# SCH_dupe_2026-03-27.net
KiCad netlist of a schematic drawn in EasyEDA
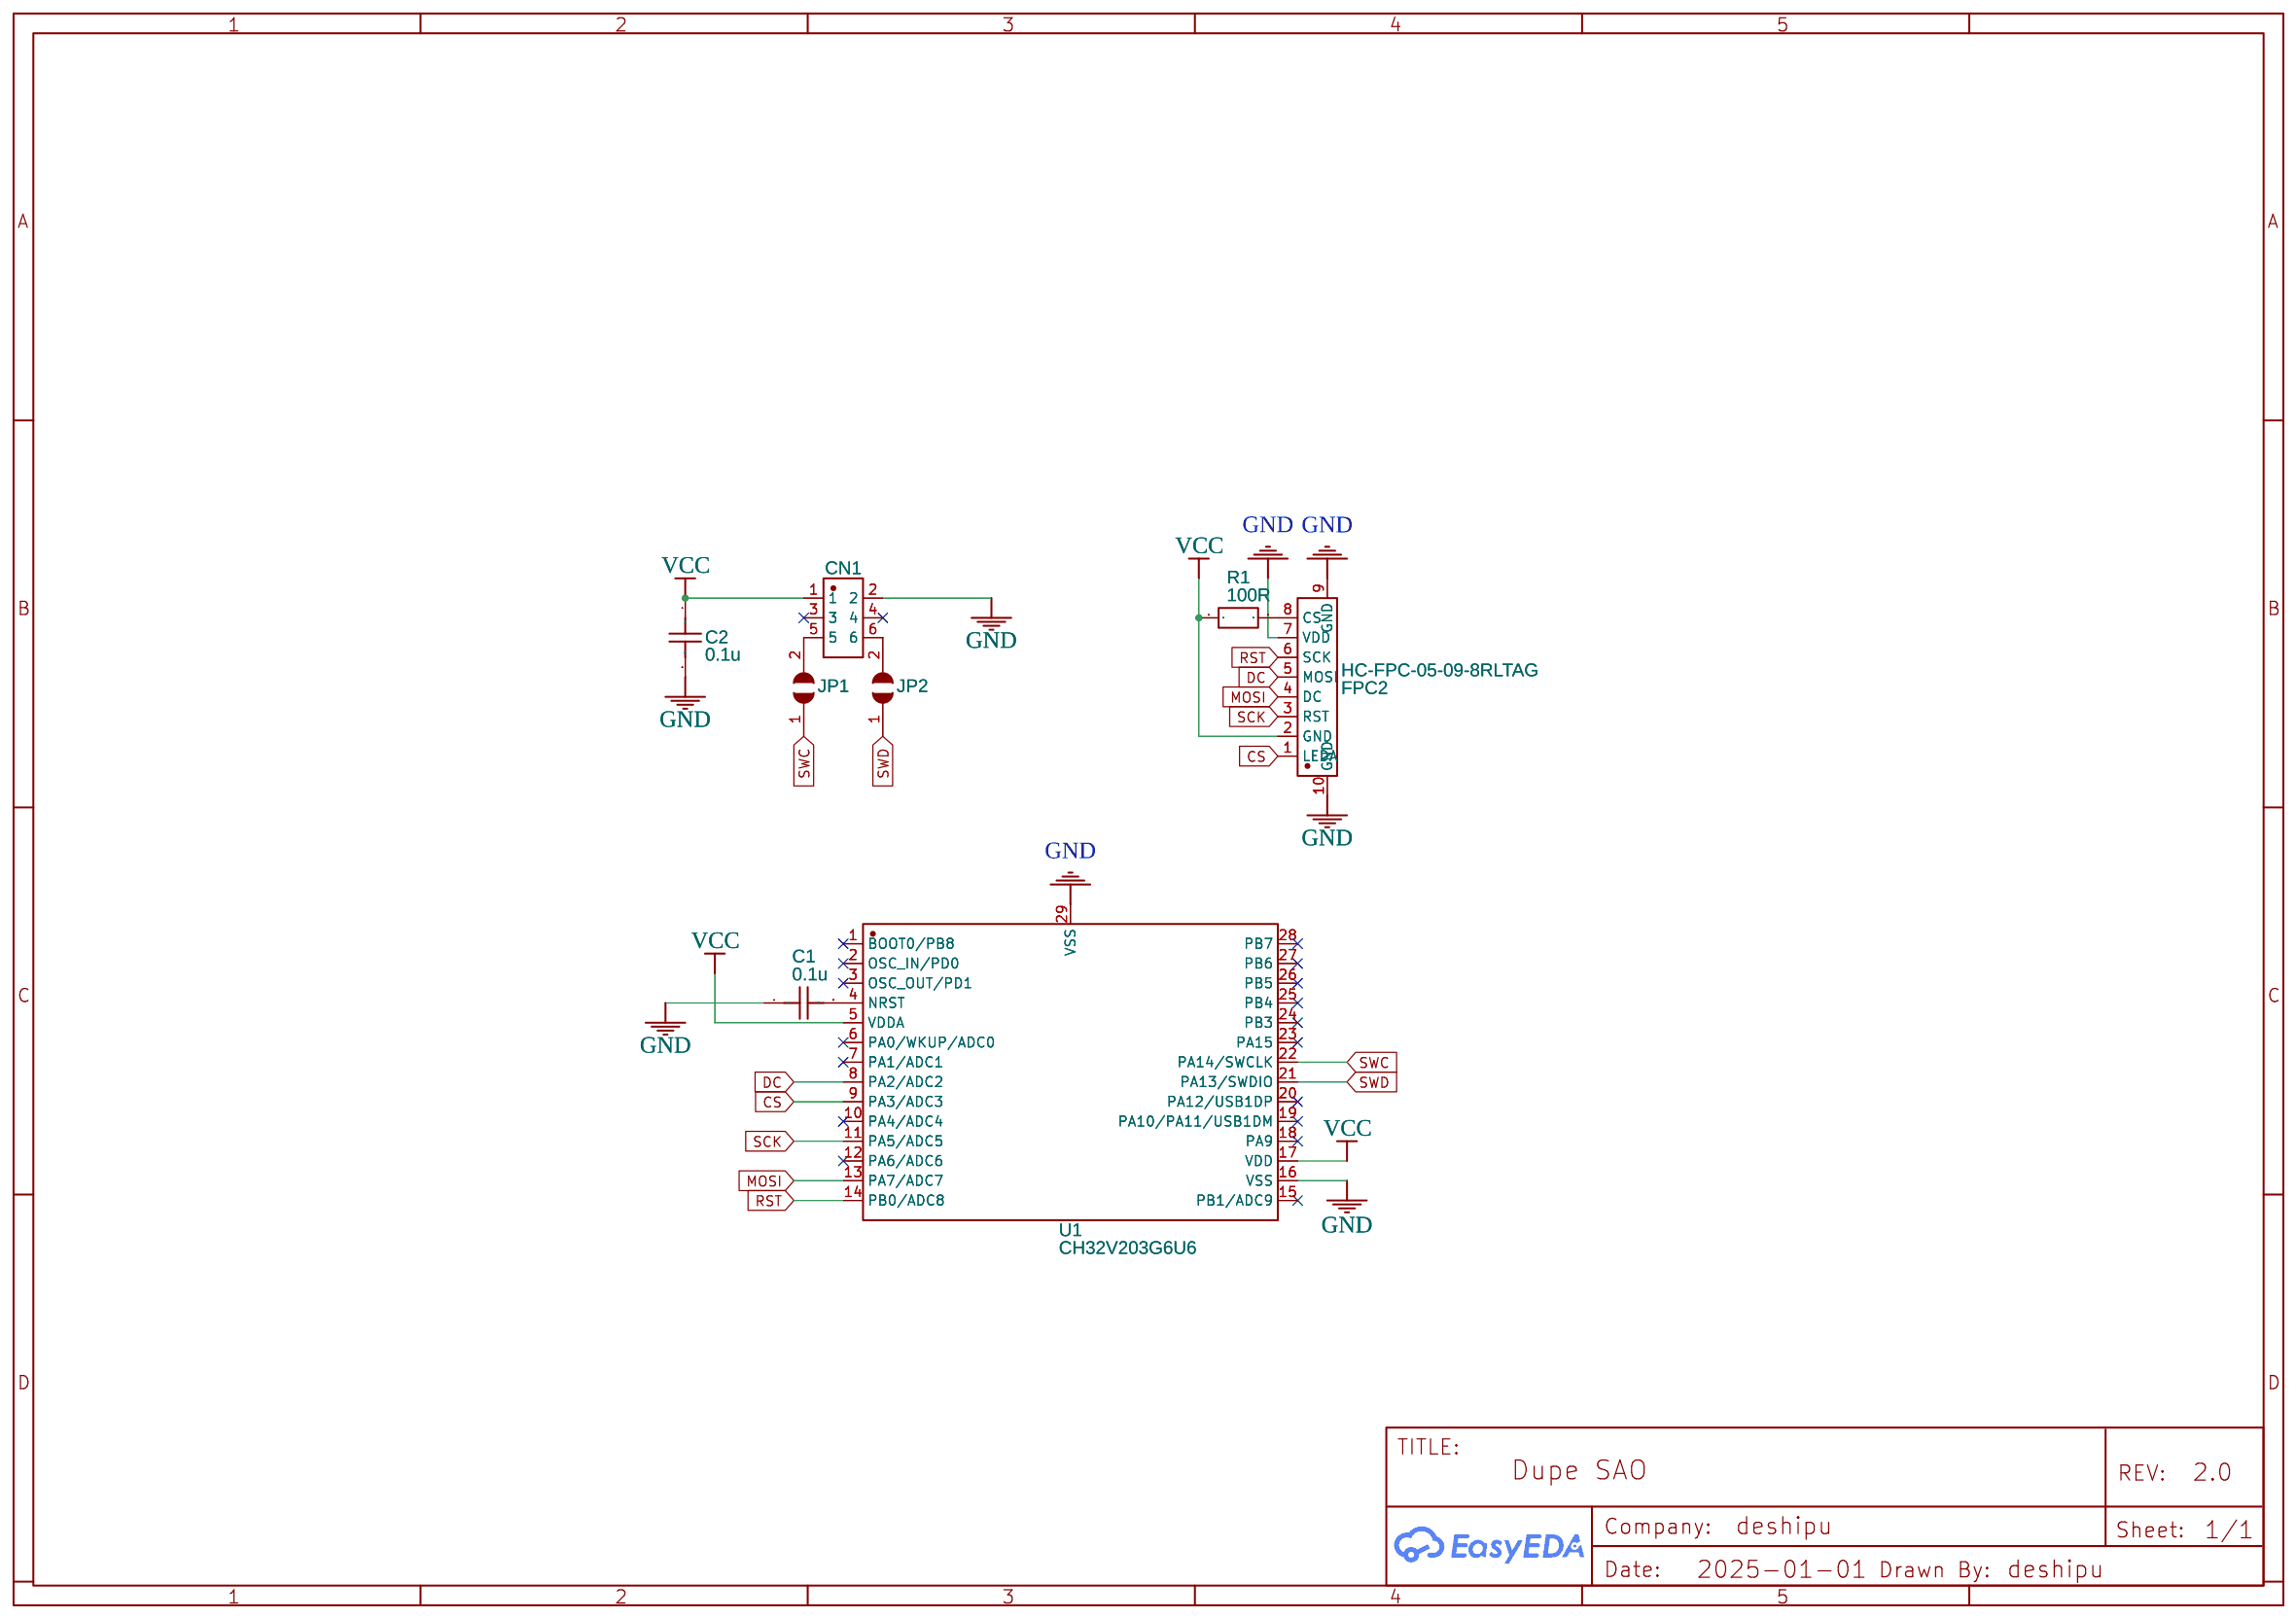
[diagram p0: schematic sheet]

(export (version "E")
  (design (tool "Eeschema 10.0.6"))
  (components
    (comp (ref "C1") (value "0.1u") (libsource (lib "") (part "C_0603_US")))
    (comp (ref "C2") (value "0.1u") (libsource (lib "") (part "C_0603_US_1")))
    (comp (ref "CN1")
      (value "BH254VS-6P")
      (fields (field (name "Manufacturer") "XFCN(兴飞)"))
      (libsource (lib "") (part "BH254VS-6P"))
    )
    (comp (ref "FPC2")
      (value "HC-FPC-05-09-8RLTAG")
      (fields (field (name "Manufacturer") "HCTL(华灿天禄)"))
      (libsource (lib "") (part "HC-FPC-05-09-8RLTAG"))
    )
    (comp (ref "JP1")
      (value "JUMPER-1-WAY-RocketScreamKicadLibrary")
      (libsource (lib "") (part "JUMPER-1-WAY-RocketScreamKicadLibrary"))
    )
    (comp (ref "JP2")
      (value "JUMPER-1-WAY-RocketScreamKicadLibrary")
      (libsource (lib "") (part "JUMPER-1-WAY-RocketScreamKicadLibrary"))
    )
    (comp (ref "R1") (value "100R") (libsource (lib "") (part "R_0603_EU")))
    (comp (ref "U1")
      (value "CH32V203G6U6")
      (fields (field (name "Manufacturer") "WCH(南京沁恒)"))
      (libsource (lib "") (part "CH32V203G6U6"))
    )
  )
  (nets
    (net (code "1") (name "CS") (class "Default")
      (node (ref "FPC2") (pin "1") (pinfunction "LEDA_1") (pintype "unspecified"))
      (node (ref "U1") (pin "9") (pinfunction "PA3/ADC3_9") (pintype "unspecified"))
    )
    (net (code "2") (name "DC") (class "Default")
      (node (ref "FPC2") (pin "5") (pinfunction "MOSI_5") (pintype "unspecified"))
      (node (ref "U1") (pin "8") (pinfunction "PA2/ADC2_8") (pintype "unspecified"))
    )
    (net (code "3") (name "GND") (class "Default")
      (node (ref "C1") (pin "1") (pinfunction "1_1") (pintype "unspecified"))
      (node (ref "C2") (pin "2") (pinfunction "2_2") (pintype "unspecified"))
      (node (ref "CN1") (pin "2") (pinfunction "2_2") (pintype "unspecified"))
      (node (ref "FPC2") (pin "10") (pinfunction "GND_10") (pintype "unspecified"))
      (node (ref "FPC2") (pin "7") (pinfunction "VDD_7") (pintype "unspecified"))
      (node (ref "FPC2") (pin "9") (pinfunction "GND_9") (pintype "unspecified"))
      (node (ref "U1") (pin "16") (pinfunction "VSS_16") (pintype "unspecified"))
      (node (ref "U1") (pin "29") (pinfunction "VSS_29") (pintype "unspecified"))
    )
    (net (code "4") (name "MOSI") (class "Default")
      (node (ref "FPC2") (pin "4") (pinfunction "DC_4") (pintype "unspecified"))
      (node (ref "U1") (pin "13") (pinfunction "PA7/ADC7_13") (pintype "unspecified"))
    )
    (net (code "5") (name "Net-(CN1-Pad5)") (class "Default")
      (node (ref "CN1") (pin "5") (pinfunction "5_5") (pintype "unspecified"))
      (node (ref "JP1") (pin "2") (pintype "unspecified"))
    )
    (net (code "6") (name "Net-(CN1-Pad6)") (class "Default")
      (node (ref "CN1") (pin "6") (pinfunction "6_6") (pintype "unspecified"))
      (node (ref "JP2") (pin "2") (pintype "unspecified"))
    )
    (net (code "7") (name "Net-(FPC2-CS)") (class "Default")
      (node (ref "FPC2") (pin "8") (pinfunction "CS_8") (pintype "unspecified"))
      (node (ref "R1") (pin "2") (pinfunction "2_2") (pintype "unspecified"))
    )
    (net (code "8") (name "Net-(U1-NRST)") (class "Default")
      (node (ref "C1") (pin "2") (pinfunction "2_2") (pintype "unspecified"))
      (node (ref "U1") (pin "4") (pinfunction "NRST_4") (pintype "unspecified"))
    )
    (net (code "9") (name "RST") (class "Default")
      (node (ref "FPC2") (pin "6") (pinfunction "SCK_6") (pintype "unspecified"))
      (node (ref "U1") (pin "14") (pinfunction "PB0/ADC8_14") (pintype "unspecified"))
    )
    (net (code "10") (name "SCK") (class "Default")
      (node (ref "FPC2") (pin "3") (pinfunction "RST_3") (pintype "unspecified"))
      (node (ref "U1") (pin "11") (pinfunction "PA5/ADC5_11") (pintype "unspecified"))
    )
    (net (code "11") (name "SWC") (class "Default")
      (node (ref "JP1") (pin "1") (pintype "unspecified"))
      (node (ref "U1") (pin "22") (pinfunction "PA14/SWCLK_22") (pintype "unspecified"))
    )
    (net (code "12") (name "SWD") (class "Default")
      (node (ref "JP2") (pin "1") (pintype "unspecified"))
      (node (ref "U1") (pin "21") (pinfunction "PA13/SWDIO_21") (pintype "unspecified"))
    )
    (net (code "13") (name "VCC") (class "Default")
      (node (ref "C2") (pin "1") (pinfunction "1_1") (pintype "unspecified"))
      (node (ref "CN1") (pin "1") (pinfunction "1_1") (pintype "unspecified"))
      (node (ref "FPC2") (pin "2") (pinfunction "GND_2") (pintype "unspecified"))
      (node (ref "R1") (pin "1") (pinfunction "1_1") (pintype "unspecified"))
      (node (ref "U1") (pin "17") (pinfunction "VDD_17") (pintype "unspecified"))
      (node (ref "U1") (pin "5") (pinfunction "VDDA_5") (pintype "unspecified"))
    )
    (net (code "14") (name "unconnected-(CN1-Pad3)") (class "Default")
      (node (ref "CN1") (pin "3") (pinfunction "3_3") (pintype "unspecified+no_connect"))
    )
    (net (code "15") (name "unconnected-(CN1-Pad4)") (class "Default")
      (node (ref "CN1") (pin "4") (pinfunction "4_4") (pintype "unspecified+no_connect"))
    )
    (net (code "16") (name "unconnected-(U1-BOOT0{slash}PB8-Pad1)") (class "Default")
      (node (ref "U1") (pin "1") (pinfunction "BOOT0/PB8_1") (pintype "unspecified+no_connect"))
    )
    (net (code "17") (name "unconnected-(U1-OSC_IN{slash}PD0-Pad2)") (class "Default")
      (node (ref "U1") (pin "2") (pinfunction "OSC_IN/PD0_2") (pintype "unspecified+no_connect"))
    )
    (net (code "18") (name "unconnected-(U1-OSC_OUT{slash}PD1-Pad3)") (class "Default")
      (node (ref "U1") (pin "3") (pinfunction "OSC_OUT/PD1_3") (pintype "unspecified+no_connect"))
    )
    (net (code "19") (name "unconnected-(U1-PA0{slash}WKUP{slash}ADC0-Pad6)") (class "Default")
      (node (ref "U1") (pin "6") (pinfunction "PA0/WKUP/ADC0_6") (pintype "unspecified+no_connect"))
    )
    (net (code "20") (name "unconnected-(U1-PA1{slash}ADC1-Pad7)") (class "Default")
      (node (ref "U1") (pin "7") (pinfunction "PA1/ADC1_7") (pintype "unspecified+no_connect"))
    )
    (net (code "21") (name "unconnected-(U1-PA4{slash}ADC4-Pad10)") (class "Default")
      (node (ref "U1") (pin "10") (pinfunction "PA4/ADC4_10") (pintype "unspecified+no_connect"))
    )
    (net (code "22") (name "unconnected-(U1-PA6{slash}ADC6-Pad12)") (class "Default")
      (node (ref "U1") (pin "12") (pinfunction "PA6/ADC6_12") (pintype "unspecified+no_connect"))
    )
    (net (code "23") (name "unconnected-(U1-PA9-Pad18)") (class "Default")
      (node (ref "U1") (pin "18") (pinfunction "PA9_18") (pintype "unspecified+no_connect"))
    )
    (net (code "24") (name "unconnected-(U1-PA10{slash}PA11{slash}USB1DM-Pad19)") (class "Default")
      (node (ref "U1") (pin "19") (pinfunction "PA10/PA11/USB1DM_19") (pintype "unspecified+no_connect"))
    )
    (net (code "25") (name "unconnected-(U1-PA12{slash}USB1DP-Pad20)") (class "Default")
      (node (ref "U1") (pin "20") (pinfunction "PA12/USB1DP_20") (pintype "unspecified+no_connect"))
    )
    (net (code "26") (name "unconnected-(U1-PA15-Pad23)") (class "Default")
      (node (ref "U1") (pin "23") (pinfunction "PA15_23") (pintype "unspecified+no_connect"))
    )
    (net (code "27") (name "unconnected-(U1-PB1{slash}ADC9-Pad15)") (class "Default")
      (node (ref "U1") (pin "15") (pinfunction "PB1/ADC9_15") (pintype "unspecified+no_connect"))
    )
    (net (code "28") (name "unconnected-(U1-PB3-Pad24)") (class "Default")
      (node (ref "U1") (pin "24") (pinfunction "PB3_24") (pintype "unspecified+no_connect"))
    )
    (net (code "29") (name "unconnected-(U1-PB4-Pad25)") (class "Default")
      (node (ref "U1") (pin "25") (pinfunction "PB4_25") (pintype "unspecified+no_connect"))
    )
    (net (code "30") (name "unconnected-(U1-PB5-Pad26)") (class "Default")
      (node (ref "U1") (pin "26") (pinfunction "PB5_26") (pintype "unspecified+no_connect"))
    )
    (net (code "31") (name "unconnected-(U1-PB6-Pad27)") (class "Default")
      (node (ref "U1") (pin "27") (pinfunction "PB6_27") (pintype "unspecified+no_connect"))
    )
    (net (code "32") (name "unconnected-(U1-PB7-Pad28)") (class "Default")
      (node (ref "U1") (pin "28") (pinfunction "PB7_28") (pintype "unspecified+no_connect"))
    )
  )
)
